# riffle-base-simple.net
KiCad netlist of a schematic drawn in EAGLE
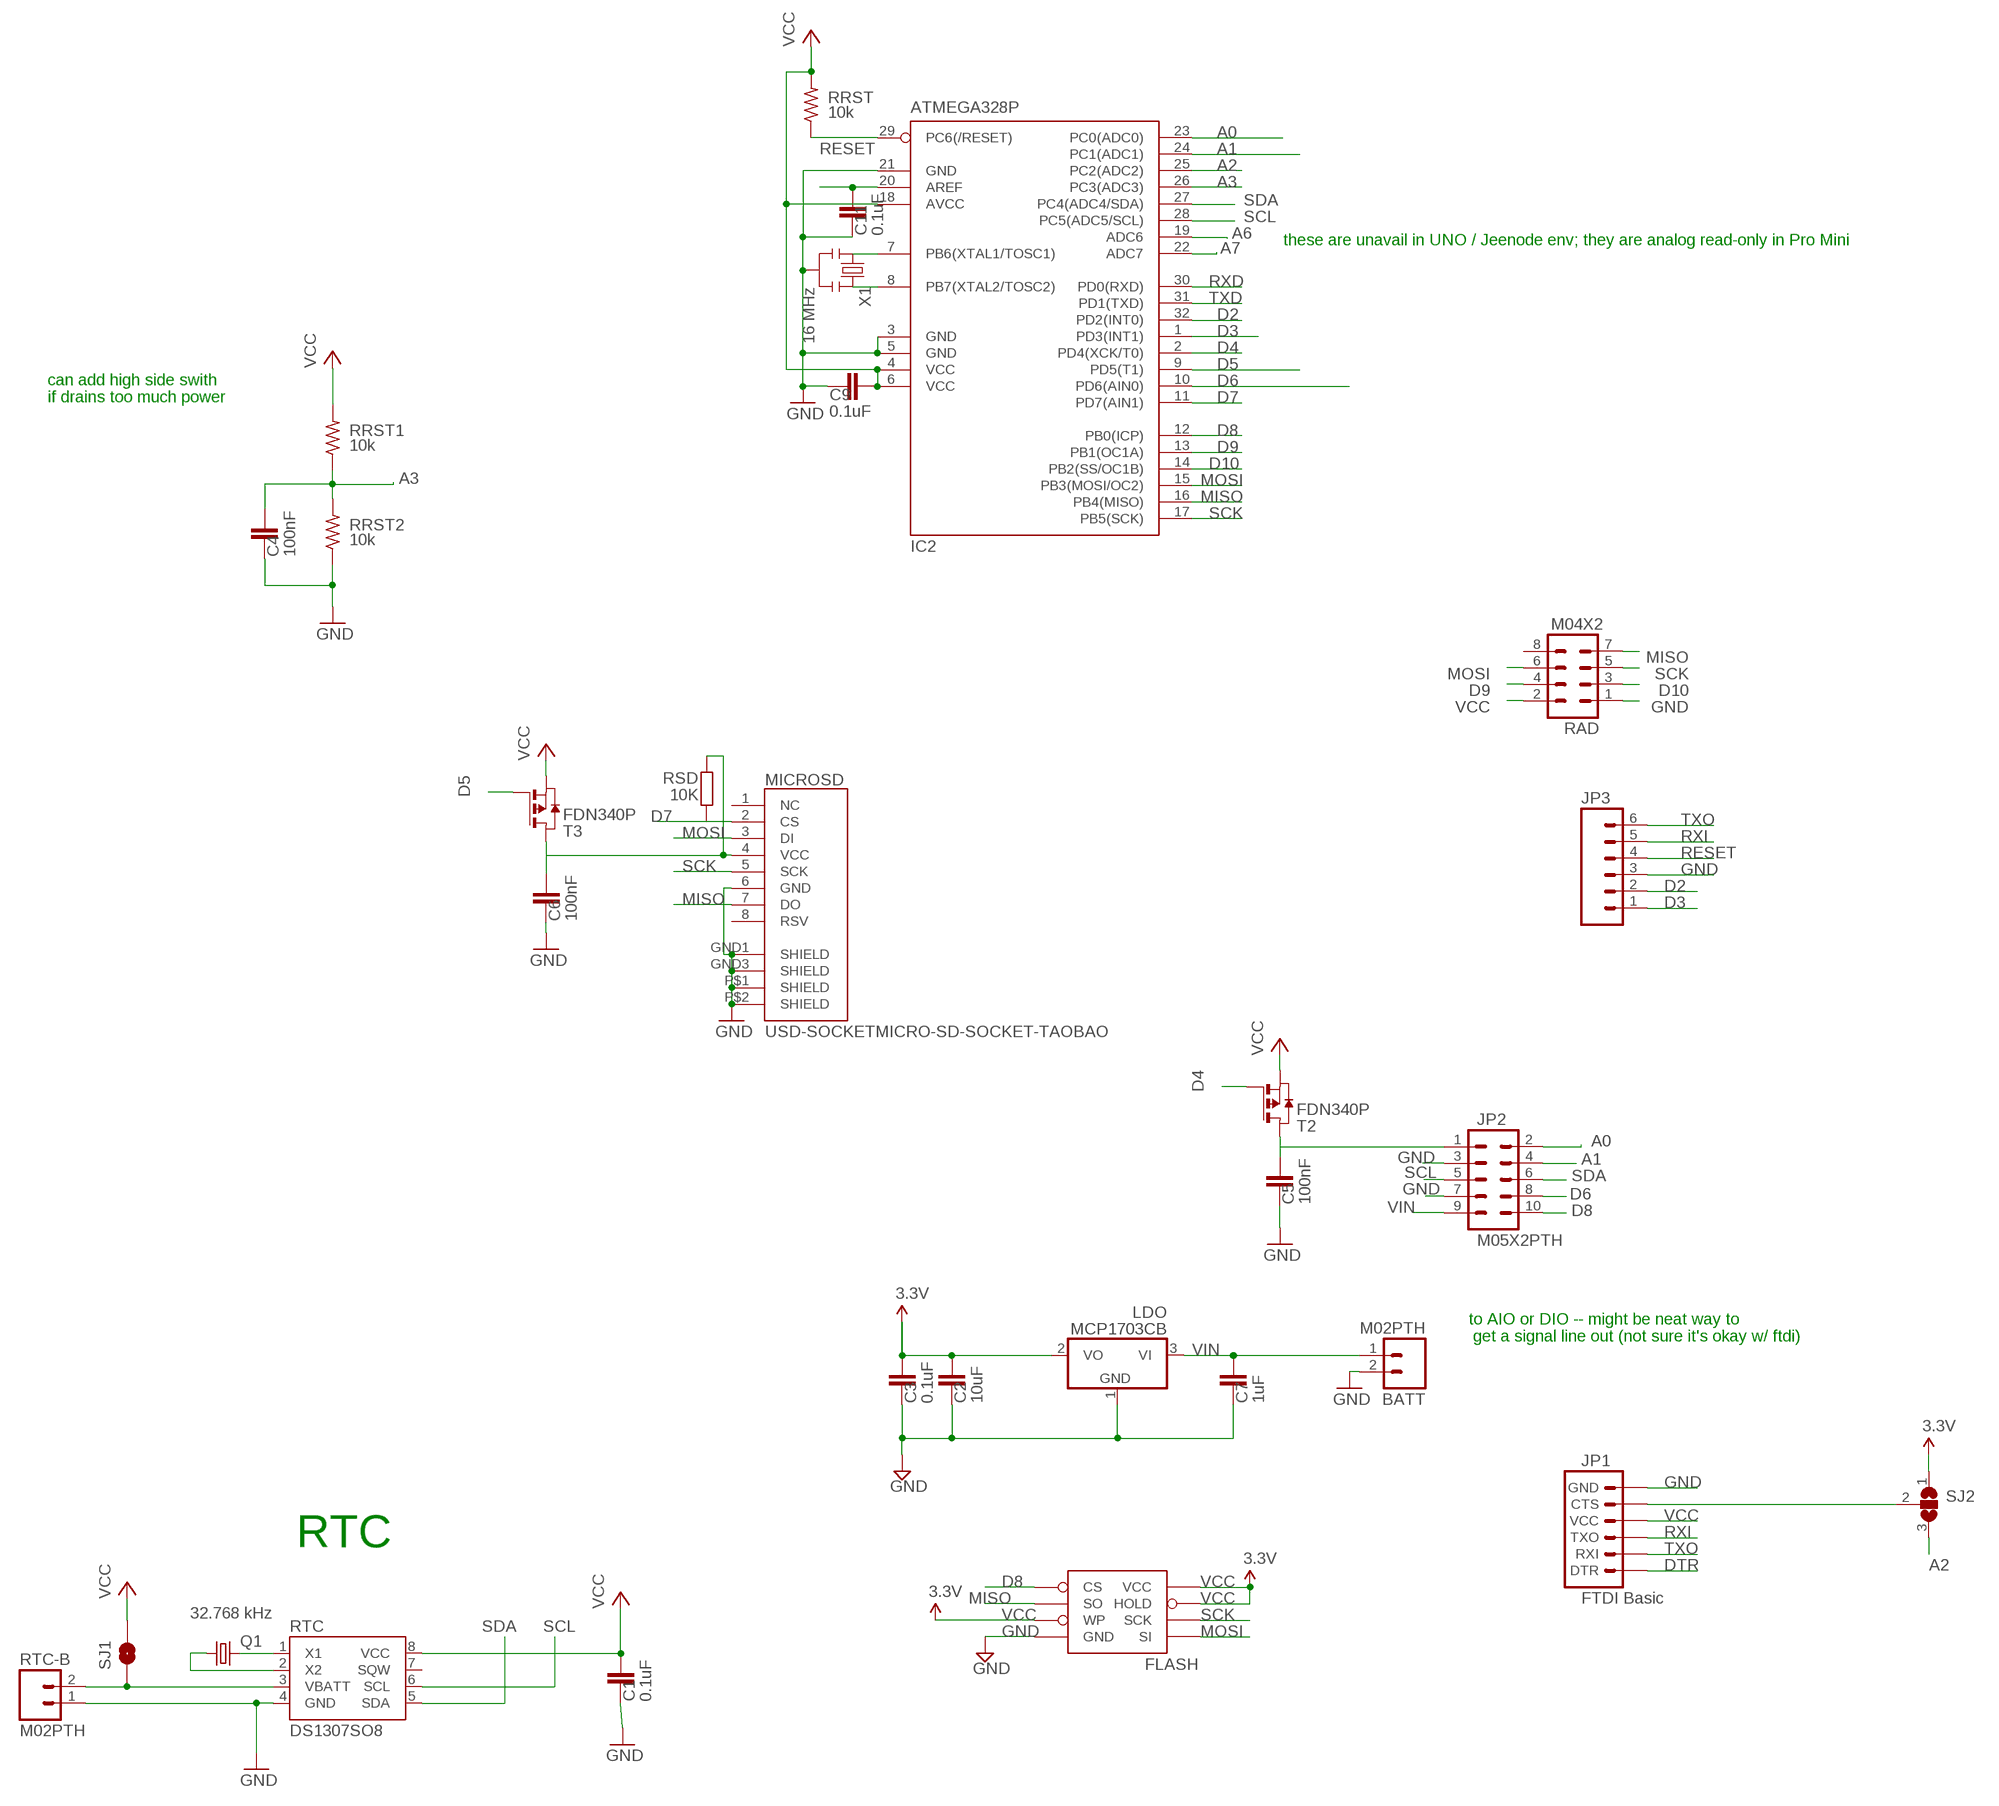
[diagram p0: schematic, sheet 1]

(export (version "E")
  (design (tool "Eeschema 10.0.6"))
  (components
    (comp (ref "BATT")
      (value "M02PTH")
      (footprint "eagle-import:1X02")
      (libsource (lib "eagle-import") (part "M02PTH"))
    )
    (comp (ref "C1")
      (value "0.1uF")
      (footprint "eagle-import:C0805")
      (libsource (lib "eagle-import") (part "C-EUC0805"))
    )
    (comp (ref "C2")
      (value "10uF")
      (footprint "eagle-import:C0805")
      (libsource (lib "eagle-import") (part "C-EUC0805"))
    )
    (comp (ref "C3")
      (value "0.1uF")
      (footprint "eagle-import:C0805")
      (libsource (lib "eagle-import") (part "C-EUC0805"))
    )
    (comp (ref "C4")
      (value "100nF")
      (footprint "eagle-import:C0805")
      (libsource (lib "eagle-import") (part "C-EUC0805"))
    )
    (comp (ref "C5")
      (value "100nF")
      (footprint "eagle-import:C0805")
      (libsource (lib "eagle-import") (part "C-EUC0805"))
    )
    (comp (ref "C6")
      (value "100nF")
      (footprint "eagle-import:C0805")
      (libsource (lib "eagle-import") (part "C-EUC0805"))
    )
    (comp (ref "C7")
      (value "1uF")
      (footprint "eagle-import:C0805")
      (libsource (lib "eagle-import") (part "C-EUC0805"))
    )
    (comp (ref "C9")
      (value "0.1uF")
      (footprint "eagle-import:C0805")
      (libsource (lib "eagle-import") (part "C-EUC0805"))
    )
    (comp (ref "C11")
      (value "0.1uF")
      (footprint "eagle-import:C0805")
      (libsource (lib "eagle-import") (part "C-EUC0805"))
    )
    (comp (ref "FLASH")
      (value "AT25F512BWIDE_5.3MM")
      (footprint "eagle-import:SO08WIDE")
      (libsource (lib "eagle-import") (part "AT25F512BWIDE_5.3MM"))
    )
    (comp (ref "IC2")
      (value "ATMEGA328P")
      (footprint "eagle-import:TQFP32-08")
      (fields (field (name "MPN") "ATMEGA8-16AU"))
      (libsource (lib "eagle-import") (part "MEGA8-AI"))
    )
    (comp (ref "JP1")
      (value "FTDI Basic")
      (footprint "eagle-import:1X06")
      (libsource (lib "eagle-import") (part "ARDUINO_SERIAL_PROGRAMPTH"))
    )
    (comp (ref "JP2")
      (value "M05X2PTH")
      (footprint "eagle-import:AVR_ICSP")
      (libsource (lib "eagle-import") (part "M05X2PTH"))
    )
    (comp (ref "JP3")
      (value "M06LOCK")
      (footprint "eagle-import:1X06_LOCK")
      (libsource (lib "eagle-import") (part "M06LOCK"))
    )
    (comp (ref "LDO")
      (value "MCP1703CB")
      (footprint "eagle-import:SOT23")
      (libsource (lib "eagle-import") (part "MCP1703CB"))
    )
    (comp (ref "MICROSD")
      (value "USD-SOCKETMICRO-SD-SOCKET-TAOBAO")
      (footprint "eagle-import:MICRO-SD-SOCKET-TAOBAO")
      (libsource (lib "eagle-import") (part "USD-SOCKETMICRO-SD-SOCKET-TAOBAO"))
    )
    (comp (ref "Q1")
      (value "32.768 kHz")
      (footprint "eagle-import:TC26H")
      (libsource (lib "eagle-import") (part "CRYSTALTC26H"))
    )
    (comp (ref "RAD")
      (value "M04X2")
      (footprint "eagle-import:2X4")
      (libsource (lib "eagle-import") (part "M04X2"))
    )
    (comp (ref "RRST")
      (value "10k")
      (footprint "eagle-import:R0805@1")
      (libsource (lib "eagle-import") (part "R-US_R0805"))
    )
    (comp (ref "RRST1")
      (value "10k")
      (footprint "eagle-import:R0805@1")
      (libsource (lib "eagle-import") (part "R-US_R0805"))
    )
    (comp (ref "RRST2")
      (value "10k")
      (footprint "eagle-import:R0805@1")
      (libsource (lib "eagle-import") (part "R-US_R0805"))
    )
    (comp (ref "RSD")
      (value "10K")
      (footprint "eagle-import:R0805")
      (libsource (lib "eagle-import") (part "R-EU_R0805"))
    )
    (comp (ref "RTC")
      (value "DS1307SO8")
      (footprint "eagle-import:SO08")
      (libsource (lib "eagle-import") (part "DS1307SO8"))
    )
    (comp (ref "RTC-B")
      (value "M02PTH")
      (footprint "eagle-import:1X02")
      (libsource (lib "eagle-import") (part "M02PTH"))
    )
    (comp (ref "SJ1")
      (value "SOLDERJUMPERTRACE")
      (footprint "eagle-import:SJ_2S-TRACE")
      (libsource (lib "eagle-import") (part "SOLDERJUMPERTRACE"))
    )
    (comp (ref "SJ2")
      (value "SJ2W")
      (footprint "eagle-import:SJ_2")
      (libsource (lib "eagle-import") (part "SJ2W"))
    )
    (comp (ref "T2")
      (value "FDN340P")
      (footprint "eagle-import:SOT-23")
      (libsource (lib "eagle-import") (part "PMOSSOT23"))
    )
    (comp (ref "T3")
      (value "FDN340P")
      (footprint "eagle-import:SOT-23")
      (libsource (lib "eagle-import") (part "PMOSSOT23"))
    )
    (comp (ref "X1")
      (value "16 MHz")
      (footprint "eagle-import:RESONATOR-SMD")
      (libsource (lib "eagle-import") (part "RESONATORSMD"))
    )
  )
  (nets
    (net (code "1") (name "/A0") (class "Default")
      (node (ref "IC2") (pin "23") (pinfunction "PC0(ADC0)_23") (pintype "bidirectional"))
      (node (ref "JP2") (pin "2") (pinfunction "2_2") (pintype "passive"))
    )
    (net (code "2") (name "/A1") (class "Default")
      (node (ref "IC2") (pin "24") (pinfunction "PC1(ADC1)_24") (pintype "bidirectional"))
      (node (ref "JP2") (pin "4") (pinfunction "4_4") (pintype "passive"))
    )
    (net (code "3") (name "/A2") (class "Default")
      (node (ref "IC2") (pin "25") (pinfunction "PC2(ADC2)_25") (pintype "bidirectional"))
      (node (ref "SJ2") (pin "3") (pinfunction "3_3") (pintype "passive"))
    )
    (net (code "4") (name "/A3") (class "Default")
      (node (ref "C4") (pin "2") (pinfunction "2_2") (pintype "passive"))
      (node (ref "IC2") (pin "26") (pinfunction "PC3(ADC3)_26") (pintype "bidirectional"))
      (node (ref "RRST1") (pin "1") (pinfunction "1_1") (pintype "passive"))
      (node (ref "RRST2") (pin "2") (pinfunction "2_2") (pintype "passive"))
    )
    (net (code "5") (name "/A6") (class "Default")
      (node (ref "IC2") (pin "19") (pinfunction "ADC6_19") (pintype "bidirectional"))
    )
    (net (code "6") (name "/A7") (class "Default")
      (node (ref "IC2") (pin "22") (pinfunction "ADC7_22") (pintype "bidirectional"))
    )
    (net (code "7") (name "/D2") (class "Default")
      (node (ref "IC2") (pin "32") (pinfunction "PD2(INT0)_32") (pintype "bidirectional"))
      (node (ref "JP3") (pin "2") (pinfunction "2_2") (pintype "passive"))
    )
    (net (code "8") (name "/D3") (class "Default")
      (node (ref "IC2") (pin "1") (pinfunction "PD3(INT1)_1") (pintype "bidirectional"))
      (node (ref "JP3") (pin "1") (pinfunction "1_1") (pintype "passive"))
    )
    (net (code "9") (name "/D4") (class "Default")
      (node (ref "IC2") (pin "2") (pinfunction "PD4(XCK/T0)_2") (pintype "bidirectional"))
      (node (ref "T2") (pin "3") (pinfunction "G_3") (pintype "passive"))
    )
    (net (code "10") (name "/D5") (class "Default")
      (node (ref "IC2") (pin "9") (pinfunction "PD5(T1)_9") (pintype "bidirectional"))
      (node (ref "T3") (pin "3") (pinfunction "G_3") (pintype "passive"))
    )
    (net (code "11") (name "/D6") (class "Default")
      (node (ref "IC2") (pin "10") (pinfunction "PD6(AIN0)_10") (pintype "bidirectional"))
      (node (ref "JP2") (pin "8") (pinfunction "8_8") (pintype "passive"))
    )
    (net (code "12") (name "/D7") (class "Default")
      (node (ref "IC2") (pin "11") (pinfunction "PD7(AIN1)_11") (pintype "bidirectional"))
      (node (ref "MICROSD") (pin "2") (pinfunction "CS_2") (pintype "bidirectional"))
      (node (ref "RSD") (pin "1") (pinfunction "1_1") (pintype "passive"))
    )
    (net (code "13") (name "/D8") (class "Default")
      (node (ref "FLASH") (pin "1") (pinfunction "CS_1") (pintype "bidirectional"))
      (node (ref "IC2") (pin "12") (pinfunction "PB0(ICP)_12") (pintype "bidirectional"))
      (node (ref "JP2") (pin "10") (pinfunction "10_10") (pintype "passive"))
    )
    (net (code "14") (name "/D9") (class "Default")
      (node (ref "IC2") (pin "13") (pinfunction "PB1(OC1A)_13") (pintype "bidirectional"))
      (node (ref "RAD") (pin "4") (pinfunction "4_4") (pintype "passive"))
    )
    (net (code "15") (name "/D10") (class "Default")
      (node (ref "IC2") (pin "14") (pinfunction "PB2(SS/OC1B)_14") (pintype "bidirectional"))
      (node (ref "RAD") (pin "3") (pinfunction "3_3") (pintype "passive"))
    )
    (net (code "16") (name "/DTR") (class "Default")
      (node (ref "JP1") (pin "1") (pinfunction "DTR_1") (pintype "passive"))
    )
    (net (code "17") (name "/MISO") (class "Default")
      (node (ref "FLASH") (pin "2") (pinfunction "SO_2") (pintype "bidirectional"))
      (node (ref "IC2") (pin "16") (pinfunction "PB4(MISO)_16") (pintype "bidirectional"))
      (node (ref "MICROSD") (pin "7") (pinfunction "DO_7") (pintype "bidirectional"))
      (node (ref "RAD") (pin "7") (pinfunction "7_7") (pintype "passive"))
    )
    (net (code "18") (name "/MOSI") (class "Default")
      (node (ref "FLASH") (pin "5") (pinfunction "SI_5") (pintype "bidirectional"))
      (node (ref "IC2") (pin "15") (pinfunction "PB3(MOSI/OC2)_15") (pintype "bidirectional"))
      (node (ref "MICROSD") (pin "3") (pinfunction "DI_3") (pintype "bidirectional"))
      (node (ref "RAD") (pin "6") (pinfunction "6_6") (pintype "passive"))
    )
    (net (code "19") (name "/RESET") (class "Default")
      (node (ref "IC2") (pin "29") (pinfunction "PC6(/RESET)_29") (pintype "bidirectional"))
      (node (ref "JP3") (pin "4") (pinfunction "4_4") (pintype "passive"))
      (node (ref "RRST") (pin "1") (pinfunction "1_1") (pintype "passive"))
    )
    (net (code "20") (name "/RXD") (class "Default")
      (node (ref "IC2") (pin "30") (pinfunction "PD0(RXD)_30") (pintype "bidirectional"))
    )
    (net (code "21") (name "/RXI") (class "Default")
      (node (ref "JP1") (pin "3") (pinfunction "TXO_3") (pintype "passive"))
      (node (ref "JP3") (pin "5") (pinfunction "5_5") (pintype "passive"))
    )
    (net (code "22") (name "/SCK") (class "Default")
      (node (ref "FLASH") (pin "6") (pinfunction "SCK_6") (pintype "bidirectional"))
      (node (ref "IC2") (pin "17") (pinfunction "PB5(SCK)_17") (pintype "bidirectional"))
      (node (ref "MICROSD") (pin "5") (pinfunction "SCK_5") (pintype "bidirectional"))
      (node (ref "RAD") (pin "5") (pinfunction "5_5") (pintype "passive"))
    )
    (net (code "23") (name "/SCL") (class "Default")
      (node (ref "IC2") (pin "28") (pinfunction "PC5(ADC5/SCL)_28") (pintype "bidirectional"))
      (node (ref "JP2") (pin "5") (pinfunction "5_5") (pintype "passive"))
      (node (ref "RTC") (pin "6") (pinfunction "SCL_6") (pintype "bidirectional"))
    )
    (net (code "24") (name "/SDA") (class "Default")
      (node (ref "IC2") (pin "27") (pinfunction "PC4(ADC4/SDA)_27") (pintype "bidirectional"))
      (node (ref "JP2") (pin "6") (pinfunction "6_6") (pintype "passive"))
      (node (ref "RTC") (pin "5") (pinfunction "SDA_5") (pintype "bidirectional"))
    )
    (net (code "25") (name "/TXD") (class "Default")
      (node (ref "IC2") (pin "31") (pinfunction "PD1(TXD)_31") (pintype "bidirectional"))
    )
    (net (code "26") (name "/TXO") (class "Default")
      (node (ref "JP1") (pin "2") (pinfunction "RXI_2") (pintype "passive"))
      (node (ref "JP3") (pin "6") (pinfunction "6_6") (pintype "passive"))
    )
    (net (code "27") (name "/VIN") (class "Default")
      (node (ref "BATT") (pin "1") (pinfunction "1_1") (pintype "passive"))
      (node (ref "C7") (pin "2") (pinfunction "2_2") (pintype "passive"))
      (node (ref "JP2") (pin "9") (pinfunction "9_9") (pintype "passive"))
      (node (ref "LDO") (pin "3") (pinfunction "VI_3") (pintype "input"))
    )
    (net (code "28") (name "3.3V") (class "Default")
      (node (ref "C1") (pin "2") (pinfunction "2_2") (pintype "passive"))
      (node (ref "C2") (pin "2") (pinfunction "2_2") (pintype "passive"))
      (node (ref "C3") (pin "2") (pinfunction "2_2") (pintype "passive"))
      (node (ref "C9") (pin "2") (pinfunction "2_2") (pintype "passive"))
      (node (ref "FLASH") (pin "3") (pinfunction "WP_3") (pintype "bidirectional"))
      (node (ref "FLASH") (pin "7") (pinfunction "HOLD_7") (pintype "bidirectional"))
      (node (ref "FLASH") (pin "8") (pinfunction "VCC_8") (pintype "bidirectional"))
      (node (ref "IC2") (pin "18") (pinfunction "AVCC_18") (pintype "power_in"))
      (node (ref "IC2") (pin "4") (pinfunction "VCC_4") (pintype "power_in"))
      (node (ref "IC2") (pin "6") (pinfunction "VCC_6") (pintype "power_in"))
      (node (ref "JP1") (pin "4") (pinfunction "VCC_4") (pintype "passive"))
      (node (ref "LDO") (pin "2") (pinfunction "VO_2") (pintype "passive"))
      (node (ref "RAD") (pin "2") (pinfunction "2_2") (pintype "passive"))
      (node (ref "RRST") (pin "2") (pinfunction "2_2") (pintype "passive"))
      (node (ref "RRST1") (pin "2") (pinfunction "2_2") (pintype "passive"))
      (node (ref "RTC") (pin "8") (pinfunction "VCC_8") (pintype "bidirectional"))
      (node (ref "SJ1") (pin "2") (pinfunction "2_2") (pintype "passive"))
      (node (ref "SJ2") (pin "1") (pinfunction "1_1") (pintype "passive"))
      (node (ref "T2") (pin "2") (pinfunction "S_2") (pintype "passive"))
      (node (ref "T3") (pin "2") (pinfunction "S_2") (pintype "passive"))
    )
    (net (code "29") (name "GND") (class "Default")
      (node (ref "BATT") (pin "2") (pinfunction "2_2") (pintype "passive"))
      (node (ref "C1") (pin "1") (pinfunction "1_1") (pintype "passive"))
      (node (ref "C11") (pin "1") (pinfunction "1_1") (pintype "passive"))
      (node (ref "C2") (pin "1") (pinfunction "1_1") (pintype "passive"))
      (node (ref "C3") (pin "1") (pinfunction "1_1") (pintype "passive"))
      (node (ref "C4") (pin "1") (pinfunction "1_1") (pintype "passive"))
      (node (ref "C5") (pin "1") (pinfunction "1_1") (pintype "passive"))
      (node (ref "C6") (pin "1") (pinfunction "1_1") (pintype "passive"))
      (node (ref "C7") (pin "1") (pinfunction "1_1") (pintype "passive"))
      (node (ref "C9") (pin "1") (pinfunction "1_1") (pintype "passive"))
      (node (ref "FLASH") (pin "4") (pinfunction "GND_4") (pintype "bidirectional"))
      (node (ref "IC2") (pin "21") (pinfunction "GND_21") (pintype "power_in"))
      (node (ref "IC2") (pin "3") (pinfunction "GND_3") (pintype "power_in"))
      (node (ref "IC2") (pin "5") (pinfunction "GND_5") (pintype "power_in"))
      (node (ref "JP1") (pin "6") (pinfunction "GND_6") (pintype "passive"))
      (node (ref "JP2") (pin "3") (pinfunction "3_3") (pintype "passive"))
      (node (ref "JP2") (pin "7") (pinfunction "7_7") (pintype "passive"))
      (node (ref "JP3") (pin "3") (pinfunction "3_3") (pintype "passive"))
      (node (ref "LDO") (pin "1") (pinfunction "GND_1") (pintype "passive"))
      (node (ref "MICROSD") (pin "6") (pinfunction "GND_6") (pintype "bidirectional"))
      (node (ref "MICROSD") (pin "GND1") (pinfunction "SHIELD_GND1") (pintype "bidirectional"))
      (node (ref "MICROSD") (pin "GND3") (pinfunction "SHIELD_GND3") (pintype "bidirectional"))
      (node (ref "MICROSD") (pin "P$1") (pinfunction "SHIELD_P$1") (pintype "bidirectional"))
      (node (ref "MICROSD") (pin "P$2") (pinfunction "SHIELD_P$2") (pintype "bidirectional"))
      (node (ref "RAD") (pin "1") (pinfunction "1_1") (pintype "passive"))
      (node (ref "RRST2") (pin "1") (pinfunction "1_1") (pintype "passive"))
      (node (ref "RTC") (pin "4") (pinfunction "GND_4") (pintype "bidirectional"))
      (node (ref "RTC-B") (pin "1") (pinfunction "1_1") (pintype "passive"))
      (node (ref "X1") (pin "2") (pinfunction "2_2") (pintype "passive"))
    )
    (net (code "30") (name "Net-(IC2-AREF)") (class "Default")
      (node (ref "C11") (pin "2") (pinfunction "2_2") (pintype "passive"))
      (node (ref "IC2") (pin "20") (pinfunction "AREF_20") (pintype "passive"))
    )
    (net (code "31") (name "Net-(IC2-PB6(XTAL1{slash}TOSC1))") (class "Default")
      (node (ref "IC2") (pin "7") (pinfunction "PB6(XTAL1/TOSC1)_7") (pintype "bidirectional"))
      (node (ref "X1") (pin "1") (pinfunction "1_1") (pintype "passive"))
    )
    (net (code "32") (name "Net-(IC2-PB7(XTAL2{slash}TOSC2))") (class "Default")
      (node (ref "IC2") (pin "8") (pinfunction "PB7(XTAL2/TOSC2)_8") (pintype "bidirectional"))
      (node (ref "X1") (pin "3") (pinfunction "3_3") (pintype "passive"))
    )
    (net (code "33") (name "Net-(JP1-CTS)") (class "Default")
      (node (ref "JP1") (pin "5") (pinfunction "CTS_5") (pintype "passive"))
      (node (ref "SJ2") (pin "2") (pinfunction "2_2") (pintype "passive"))
    )
    (net (code "34") (name "Net-(MICROSD-VCC)") (class "Default")
      (node (ref "C6") (pin "2") (pinfunction "2_2") (pintype "passive"))
      (node (ref "MICROSD") (pin "4") (pinfunction "VCC_4") (pintype "bidirectional"))
      (node (ref "RSD") (pin "2") (pinfunction "2_2") (pintype "passive"))
      (node (ref "T3") (pin "1") (pinfunction "D_1") (pintype "passive"))
    )
    (net (code "35") (name "Net-(RTC-VBATT)") (class "Default")
      (node (ref "RTC") (pin "3") (pinfunction "VBATT_3") (pintype "bidirectional"))
      (node (ref "RTC-B") (pin "2") (pinfunction "2_2") (pintype "passive"))
      (node (ref "SJ1") (pin "1") (pinfunction "1_1") (pintype "passive"))
    )
    (net (code "36") (name "Net-(RTC-X1)") (class "Default")
      (node (ref "Q1") (pin "2") (pinfunction "2_2") (pintype "passive"))
      (node (ref "RTC") (pin "1") (pinfunction "X1_1") (pintype "bidirectional"))
    )
    (net (code "37") (name "Net-(RTC-X2)") (class "Default")
      (node (ref "Q1") (pin "1") (pinfunction "1_1") (pintype "passive"))
      (node (ref "RTC") (pin "2") (pinfunction "X2_2") (pintype "bidirectional"))
    )
    (net (code "38") (name "Net-(T2-D)") (class "Default")
      (node (ref "C5") (pin "2") (pinfunction "2_2") (pintype "passive"))
      (node (ref "JP2") (pin "1") (pinfunction "1_1") (pintype "passive"))
      (node (ref "T2") (pin "1") (pinfunction "D_1") (pintype "passive"))
    )
    (net (code "39") (name "unconnected-(MICROSD-NC-Pad1)") (class "Default")
      (node (ref "MICROSD") (pin "1") (pinfunction "NC_1") (pintype "bidirectional"))
    )
    (net (code "40") (name "unconnected-(MICROSD-RSV-Pad8)") (class "Default")
      (node (ref "MICROSD") (pin "8") (pinfunction "RSV_8") (pintype "bidirectional"))
    )
    (net (code "41") (name "unconnected-(RAD-Pad8)") (class "Default")
      (node (ref "RAD") (pin "8") (pinfunction "8_8") (pintype "passive"))
    )
    (net (code "42") (name "unconnected-(RTC-SQW-Pad7)") (class "Default")
      (node (ref "RTC") (pin "7") (pinfunction "SQW_7") (pintype "bidirectional"))
    )
  )
)
